# BNO055.net
KiCad netlist of a schematic drawn in Altium Designer
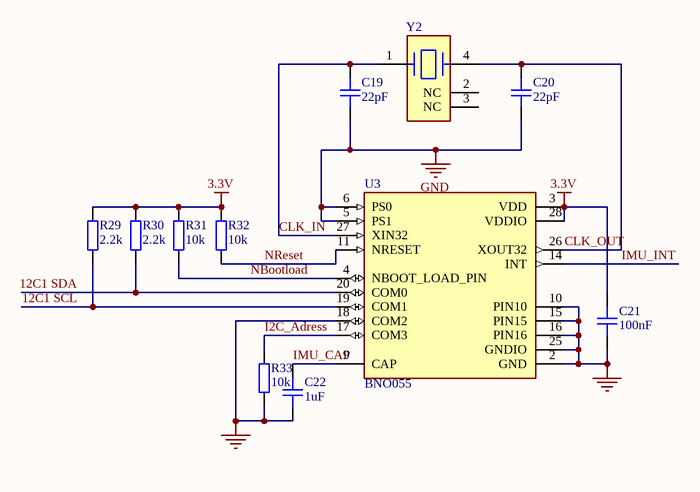
[diagram p0: BNO055.SchDoc]

(export (version "E")
  (design (tool "Eeschema 10.0.6"))
  (components
    (comp (ref "C19")
      (value "22pF")
      (footprint "CAP_0603")
      (description "Capacitor SMD 0603")
      (libsource (lib "Schematic-Lib-PhilsLab") (part "CAP_0603"))
    )
    (comp (ref "C20")
      (value "22pF")
      (footprint "CAP_0603")
      (description "Capacitor SMD 0603")
      (libsource (lib "Schematic-Lib-PhilsLab") (part "CAP_0603"))
    )
    (comp (ref "C21")
      (value "100nF")
      (footprint "CAP_0603")
      (description "Capacitor SMD 0603")
      (libsource (lib "Schematic-Lib-PhilsLab") (part "CAP_0603"))
    )
    (comp (ref "C22")
      (value "1uF")
      (footprint "CAP_0603")
      (description "Capacitor SMD 0603")
      (libsource (lib "Schematic-Lib-PhilsLab") (part "CAP_0603"))
    )
    (comp (ref "R29")
      (value "2.2k")
      (footprint "RES_0603")
      (description "Resistor SMD 0603")
      (libsource (lib "Schematic-Lib-PhilsLab") (part "RES_0603"))
    )
    (comp (ref "R30")
      (value "2.2k")
      (footprint "RES_0603")
      (description "Resistor SMD 0603")
      (libsource (lib "Schematic-Lib-PhilsLab") (part "RES_0603"))
    )
    (comp (ref "R31")
      (value "10k")
      (footprint "RES_0603")
      (description "Resistor SMD 0603")
      (libsource (lib "Schematic-Lib-PhilsLab") (part "RES_0603"))
    )
    (comp (ref "R32")
      (value "10k")
      (footprint "RES_0603")
      (description "Resistor SMD 0603")
      (libsource (lib "Schematic-Lib-PhilsLab") (part "RES_0603"))
    )
    (comp (ref "R33")
      (value "10k")
      (footprint "RES_0603")
      (description "Resistor SMD 0603")
      (libsource (lib "Schematic-Lib-PhilsLab") (part "RES_0603"))
    )
    (comp (ref "U3")
      (value "BNO055")
      (footprint "LGA28R50P4X10_380X520X100")
      (description "BNO055 9-axis Absolute Orientation Sensor ( SiP ) w/Sensors and Sensor Fusion")
      (libsource (lib "BNO055") (part "BNO055"))
    )
    (comp (ref "Y2")
      (value "ABS25-32.768KHZ-T")
      (footprint "FP-ABS25-MFG")
      (description "CRYSTAL 32.7680KHZ 12.5PF SMD")
      (fields (field (name "TOLERANCE") "20ppm"))
      (libsource (lib "Altium Content Vault") (part "d2378e42ab3755ffcd472789242ec61"))
    )
  )
  (nets
    (net (code "1") (name "/12C1 SCL") (class "Default")
      (node (ref "R29") (pin "2") (pinfunction "2_2") (pintype "passive"))
      (node (ref "U3") (pin "19") (pinfunction "COM1_19") (pintype "bidirectional"))
    )
    (net (code "2") (name "/12C1 SDA") (class "Default")
      (node (ref "R30") (pin "2") (pinfunction "2_2") (pintype "passive"))
      (node (ref "U3") (pin "20") (pinfunction "COM0_20") (pintype "bidirectional"))
    )
    (net (code "3") (name "/CLK_IN") (class "Default")
      (node (ref "C19") (pin "2") (pinfunction "2_2") (pintype "passive"))
      (node (ref "U3") (pin "27") (pinfunction "XIN32_27") (pintype "input"))
      (node (ref "Y2") (pin "1") (pinfunction "1_1") (pintype "passive"))
    )
    (net (code "4") (name "/CLK_OUT") (class "Default")
      (node (ref "C20") (pin "2") (pinfunction "2_2") (pintype "passive"))
      (node (ref "U3") (pin "26") (pinfunction "XOUT32_26") (pintype "output"))
      (node (ref "Y2") (pin "4") (pinfunction "4_4") (pintype "passive"))
    )
    (net (code "5") (name "/I2C_Adress") (class "Default")
      (node (ref "R33") (pin "1") (pinfunction "1_1") (pintype "passive"))
      (node (ref "U3") (pin "17") (pinfunction "COM3_17") (pintype "bidirectional"))
    )
    (net (code "6") (name "/IMU_CAP") (class "Default")
      (node (ref "C22") (pin "2") (pinfunction "2_2") (pintype "passive"))
      (node (ref "U3") (pin "9") (pinfunction "CAP_9") (pintype "passive"))
    )
    (net (code "7") (name "/IMU_INT") (class "Default")
      (node (ref "U3") (pin "14") (pinfunction "INT_14") (pintype "output"))
    )
    (net (code "8") (name "/NBootload") (class "Default")
      (node (ref "R31") (pin "2") (pinfunction "2_2") (pintype "passive"))
      (node (ref "U3") (pin "4") (pinfunction "NBOOT_LOAD_PIN_4") (pintype "bidirectional"))
    )
    (net (code "9") (name "/NReset") (class "Default")
      (node (ref "R32") (pin "2") (pinfunction "2_2") (pintype "passive"))
      (node (ref "U3") (pin "11") (pinfunction "NRESET_11") (pintype "input"))
    )
    (net (code "10") (name "3.3V") (class "Default")
      (node (ref "C21") (pin "2") (pinfunction "2_2") (pintype "passive"))
      (node (ref "R29") (pin "1") (pinfunction "1_1") (pintype "passive"))
      (node (ref "R30") (pin "1") (pinfunction "1_1") (pintype "passive"))
      (node (ref "R31") (pin "1") (pinfunction "1_1") (pintype "passive"))
      (node (ref "R32") (pin "1") (pinfunction "1_1") (pintype "passive"))
      (node (ref "U3") (pin "28") (pinfunction "VDDIO_28") (pintype "power_in"))
      (node (ref "U3") (pin "3") (pinfunction "VDD_3") (pintype "power_in"))
    )
    (net (code "11") (name "GND") (class "Default")
      (node (ref "C19") (pin "1") (pinfunction "1_1") (pintype "passive"))
      (node (ref "C20") (pin "1") (pinfunction "1_1") (pintype "passive"))
      (node (ref "C21") (pin "1") (pinfunction "1_1") (pintype "passive"))
      (node (ref "C22") (pin "1") (pinfunction "1_1") (pintype "passive"))
      (node (ref "R33") (pin "2") (pinfunction "2_2") (pintype "passive"))
      (node (ref "U3") (pin "10") (pinfunction "PIN10_10") (pintype "power_in"))
      (node (ref "U3") (pin "15") (pinfunction "PIN15_15") (pintype "power_in"))
      (node (ref "U3") (pin "16") (pinfunction "PIN16_16") (pintype "power_in"))
      (node (ref "U3") (pin "18") (pinfunction "COM2_18") (pintype "bidirectional"))
      (node (ref "U3") (pin "2") (pinfunction "GND_2") (pintype "power_in"))
      (node (ref "U3") (pin "25") (pinfunction "GNDIO_25") (pintype "power_in"))
      (node (ref "U3") (pin "5") (pinfunction "PS1_5") (pintype "input"))
      (node (ref "U3") (pin "6") (pinfunction "PS0_6") (pintype "input"))
    )
    (net (code "12") (name "unconnected-(Y2-NC-Pad2)") (class "Default")
      (node (ref "Y2") (pin "2") (pinfunction "NC_2") (pintype "passive"))
    )
    (net (code "13") (name "unconnected-(Y2-NC-Pad3)") (class "Default")
      (node (ref "Y2") (pin "3") (pinfunction "NC_3") (pintype "passive"))
    )
  )
)
